# iot_ambilamp.net
KiCad netlist of a schematic drawn in EAGLE
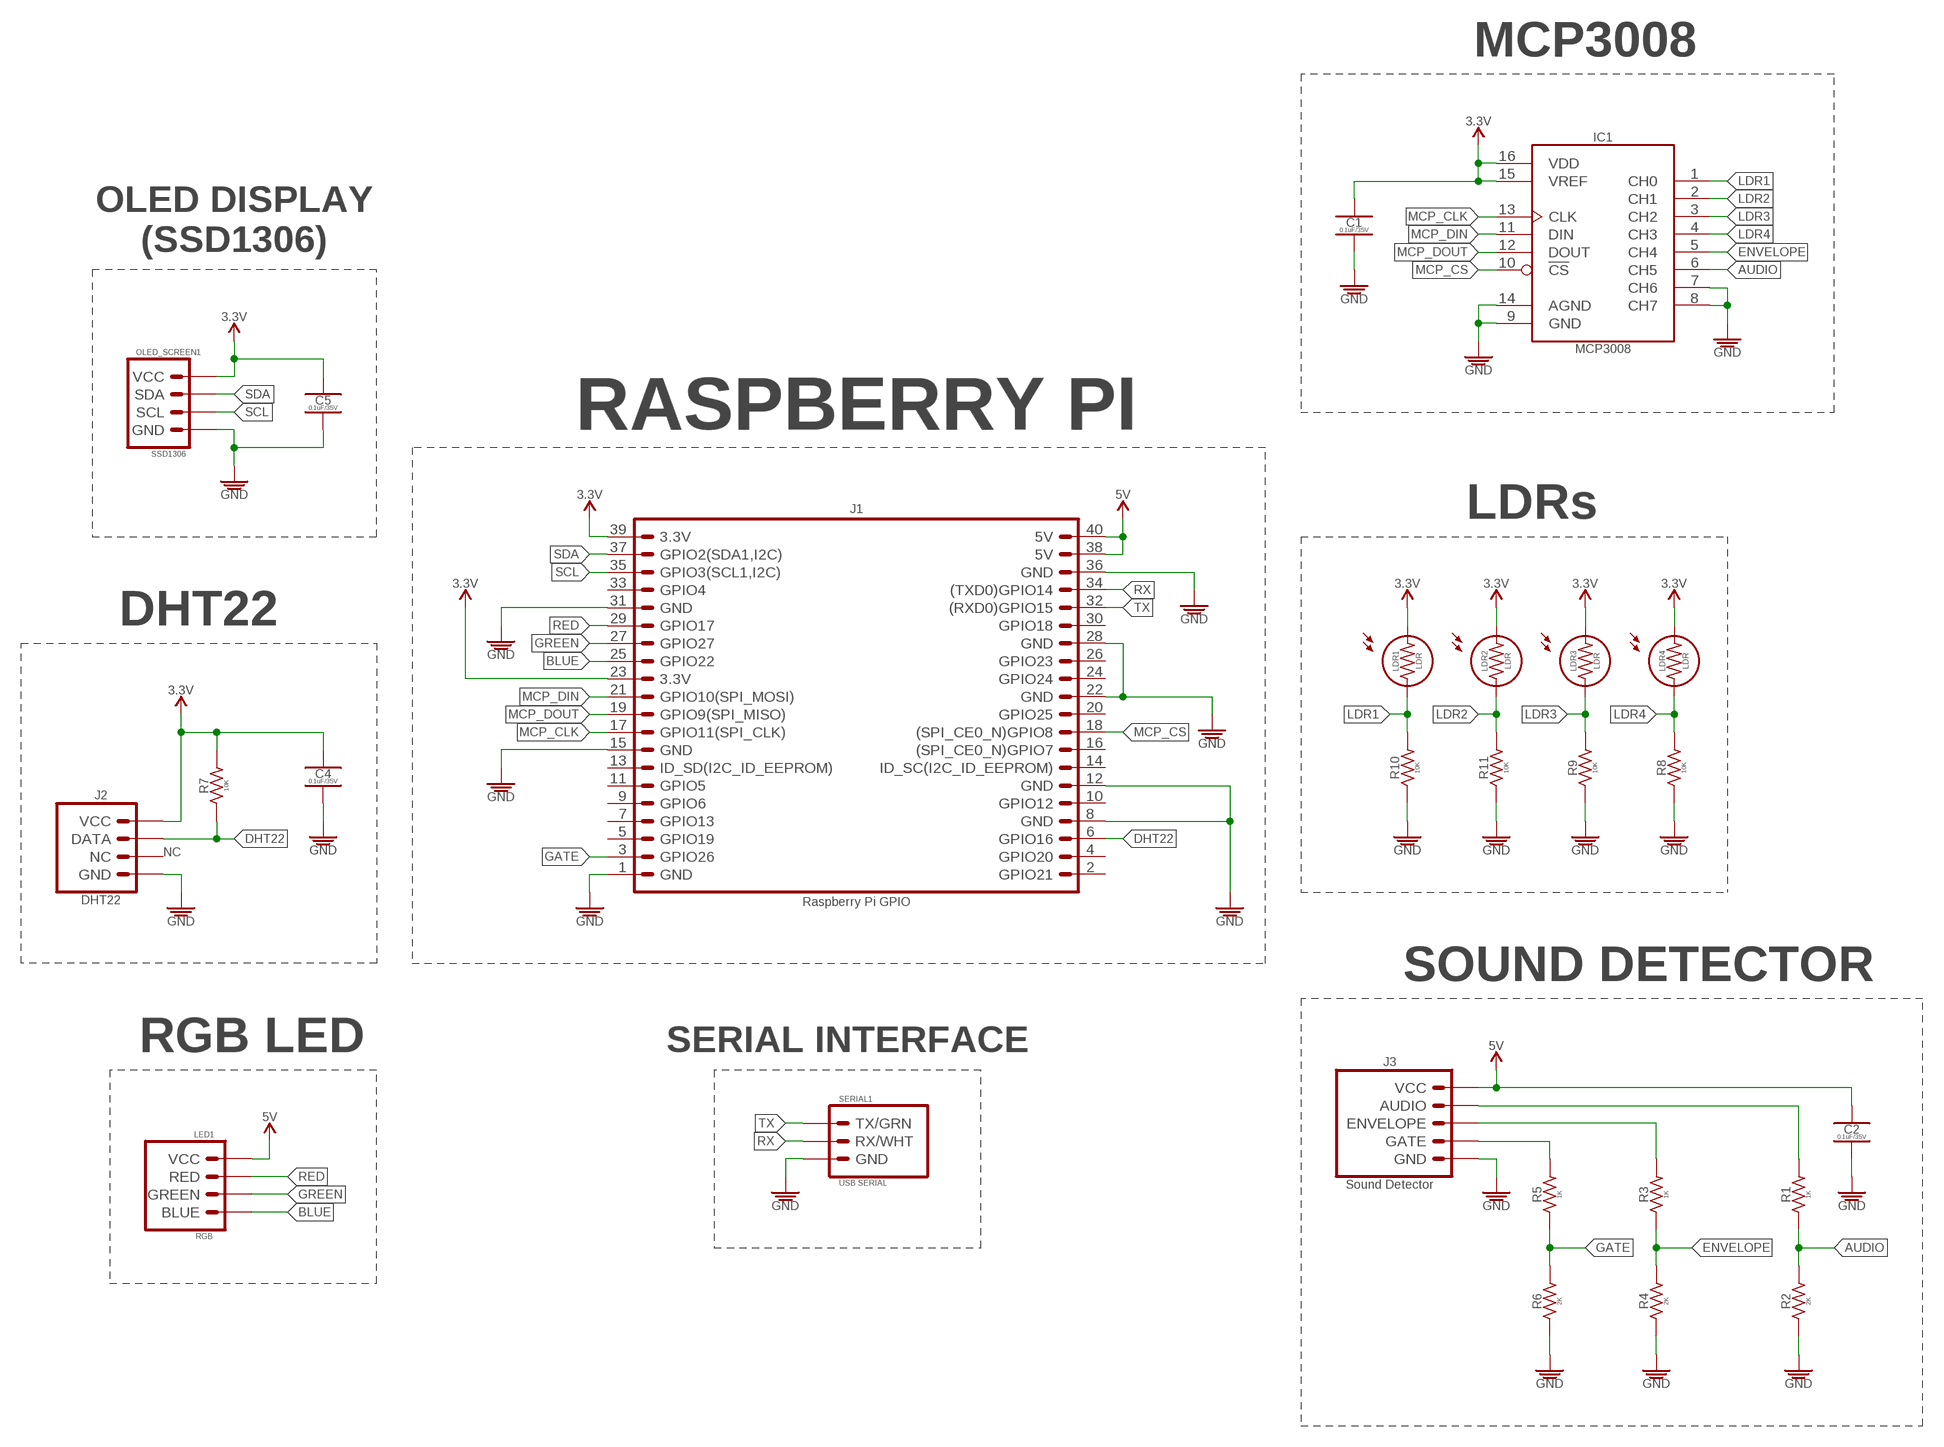
[diagram p0: schematic, sheet 1]

(export (version "E")
  (design (tool "Eeschema 10.0.6"))
  (components
    (comp (ref "C1")
      (value "0.1uF/35V")
      (footprint "eagle-import:CAPC2012X95_SMD-0805")
      (fields (field (name "MFR") "Taiyo Yuden") (field (name "MPN") "GMK212BJ104KGHT"))
      (libsource (lib "eagle-import") (part "0.1UF_SMD-0805_35V-10%"))
    )
    (comp (ref "C2")
      (value "0.1uF/35V")
      (footprint "eagle-import:CAPC2012X95_SMD-0805")
      (fields (field (name "MFR") "Taiyo Yuden") (field (name "MPN") "GMK212BJ104KGHT"))
      (libsource (lib "eagle-import") (part "0.1UF_SMD-0805_35V-10%"))
    )
    (comp (ref "C4")
      (value "0.1uF/35V")
      (footprint "eagle-import:CAPC2012X95_SMD-0805")
      (fields (field (name "MFR") "Taiyo Yuden") (field (name "MPN") "GMK212BJ104KGHT"))
      (libsource (lib "eagle-import") (part "0.1UF_SMD-0805_35V-10%"))
    )
    (comp (ref "C5")
      (value "0.1uF/35V")
      (footprint "eagle-import:CAPC2012X95_SMD-0805")
      (fields (field (name "MFR") "Taiyo Yuden") (field (name "MPN") "GMK212BJ104KGHT"))
      (libsource (lib "eagle-import") (part "0.1UF_SMD-0805_35V-10%"))
    )
    (comp (ref "IC1")
      (value "MCP3008")
      (footprint "eagle-import:SOIC127P600X175-16")
      (fields (field (name "MFR") "Microchip Technology") (field (name "MPN") "MCP3008-I/SL"))
      (libsource (lib "eagle-import") (part "MCP3008_ADC_8-CH_10-BIT_SOIC-16"))
    )
    (comp (ref "J1")
      (value "Raspberry Pi GPIO")
      (footprint "eagle-import:HDRVR40W64P254_2X20_5130X500X1350B")
      (fields (field (name "MFR") "SparkFun Electronics") (field (name "MPN") "PRT-14017"))
      (libsource (lib "eagle-import") (part "RPI-GPIO_CONNECTOR_PTH_VERT_FEMALE_2.54MM"))
    )
    (comp (ref "J2")
      (value "DHT22")
      (footprint "eagle-import:TEMPERATURE-SENSOR_DHT22")
      (fields (field (name "MFR") "Adafruit Industries LLC") (field (name "MPN") "385"))
      (libsource (lib "eagle-import") (part "TEMPERATURE-SENSOR_DHT22_DHT22_AM2302_TEMPERATURE-HUMIDITY"))
    )
    (comp (ref "J3")
      (value "Sound Detector")
      (footprint "eagle-import:HDRV5W64P254_1X5_1270X254X838B")
      (fields (field (name "MFR") "SparkFun Electronics") (field (name "MPN") "SEN-12642"))
      (libsource (lib "eagle-import") (part "SOUND-DETECTOR_SPARKFUN_BREAKOUT_PTH_VERT_MALE_2.54MM"))
    )
    (comp (ref "LDR1")
      (value "LDR")
      (footprint "eagle-import:PHOTORESISTOR_TALL")
      (fields (field (name "MFR") "Adafruit Industries LLC") (field (name "MPN") "161"))
      (libsource (lib "eagle-import") (part "PHOTORESISTOR_5MM_TALL"))
    )
    (comp (ref "LDR2")
      (value "LDR")
      (footprint "eagle-import:PHOTORESISTOR_TALL")
      (fields (field (name "MFR") "Adafruit Industries LLC") (field (name "MPN") "161"))
      (libsource (lib "eagle-import") (part "PHOTORESISTOR_5MM_TALL"))
    )
    (comp (ref "LDR3")
      (value "LDR")
      (footprint "eagle-import:PHOTORESISTOR_TALL")
      (fields (field (name "MFR") "Adafruit Industries LLC") (field (name "MPN") "161"))
      (libsource (lib "eagle-import") (part "PHOTORESISTOR_5MM_TALL"))
    )
    (comp (ref "LDR4")
      (value "LDR")
      (footprint "eagle-import:PHOTORESISTOR_TALL")
      (fields (field (name "MFR") "Adafruit Industries LLC") (field (name "MPN") "161"))
      (libsource (lib "eagle-import") (part "PHOTORESISTOR_5MM_TALL"))
    )
    (comp (ref "LED1")
      (value "RGB")
      (footprint "eagle-import:HDRVR4W75P254_1X4_1066X254X850B")
      (fields (field (name "MFR") "Chanzon") (field (name "MPN") "100F5T-YT-RGB-CA"))
      (libsource (lib "eagle-import") (part "LED-5MM-PTH_RGB-CA_PTH_VERT_FEMALE_2.54MM"))
    )
    (comp (ref "OLED_SCREEN1")
      (value "SSD1306")
      (footprint "eagle-import:HDRV4W64P254_1X4_1016X254X838B")
      (fields (field (name "MFR") "Makerfocus"))
      (libsource (lib "eagle-import") (part "SSD1306_OLED_SCREEN_0.96IN_W128-H64_PTH_VERT_MALE_2.54MM"))
    )
    (comp (ref "R1")
      (value "1K")
      (footprint "eagle-import:RESC2012X60_SMD-0805")
      (fields (field (name "MFR") "Yageo") (field (name "MPN") "RC0805JR-071KL"))
      (libsource (lib "eagle-import") (part "1KΩ_SMD-0805_1/8W-5%"))
    )
    (comp (ref "R2")
      (value "2K")
      (footprint "eagle-import:RESC2012X60_SMD-0805")
      (fields (field (name "MFR") "Yageo") (field (name "MPN") "RC0805JR-072KL"))
      (libsource (lib "eagle-import") (part "2KΩ_SMD-0805_1.8W-5%"))
    )
    (comp (ref "R3")
      (value "1K")
      (footprint "eagle-import:RESC2012X60_SMD-0805")
      (fields (field (name "MFR") "Yageo") (field (name "MPN") "RC0805JR-071KL"))
      (libsource (lib "eagle-import") (part "1KΩ_SMD-0805_1/8W-5%"))
    )
    (comp (ref "R4")
      (value "2K")
      (footprint "eagle-import:RESC2012X60_SMD-0805")
      (fields (field (name "MFR") "Yageo") (field (name "MPN") "RC0805JR-072KL"))
      (libsource (lib "eagle-import") (part "2KΩ_SMD-0805_1.8W-5%"))
    )
    (comp (ref "R5")
      (value "1K")
      (footprint "eagle-import:RESC2012X60_SMD-0805")
      (fields (field (name "MFR") "Yageo") (field (name "MPN") "RC0805JR-071KL"))
      (libsource (lib "eagle-import") (part "1KΩ_SMD-0805_1/8W-5%"))
    )
    (comp (ref "R6")
      (value "2K")
      (footprint "eagle-import:RESC2012X60_SMD-0805")
      (fields (field (name "MFR") "Yageo") (field (name "MPN") "RC0805JR-072KL"))
      (libsource (lib "eagle-import") (part "2KΩ_SMD-0805_1.8W-5%"))
    )
    (comp (ref "R7")
      (value "10K")
      (footprint "eagle-import:RESC2012X60_SMD-0805")
      (fields (field (name "MFR") "Yageo") (field (name "MPN") "RC0805JR-0710KL"))
      (libsource (lib "eagle-import") (part "10KΩ_SMD-0805_1/8W-5%"))
    )
    (comp (ref "R8")
      (value "10K")
      (footprint "eagle-import:RESC2012X60_SMD-0805")
      (fields (field (name "MFR") "Yageo") (field (name "MPN") "RC0805JR-0710KL"))
      (libsource (lib "eagle-import") (part "10KΩ_SMD-0805_1/8W-5%"))
    )
    (comp (ref "R9")
      (value "10K")
      (footprint "eagle-import:RESC2012X60_SMD-0805")
      (fields (field (name "MFR") "Yageo") (field (name "MPN") "RC0805JR-0710KL"))
      (libsource (lib "eagle-import") (part "10KΩ_SMD-0805_1/8W-5%"))
    )
    (comp (ref "R10")
      (value "10K")
      (footprint "eagle-import:RESC2012X60_SMD-0805")
      (fields (field (name "MFR") "Yageo") (field (name "MPN") "RC0805JR-0710KL"))
      (libsource (lib "eagle-import") (part "10KΩ_SMD-0805_1/8W-5%"))
    )
    (comp (ref "R11")
      (value "10K")
      (footprint "eagle-import:RESC2012X60_SMD-0805")
      (fields (field (name "MFR") "Yageo") (field (name "MPN") "RC0805JR-0710KL"))
      (libsource (lib "eagle-import") (part "10KΩ_SMD-0805_1/8W-5%"))
    )
    (comp (ref "SERIAL1")
      (value "USB SERIAL")
      (footprint "eagle-import:HDRV3W64P254_1X3_762X254X838B_USB-SERIAL-CABLE")
      (fields (field (name "MFR") "Adafruit Industries LLC") (field (name "MPN") "954"))
      (libsource (lib "eagle-import") (part "USB_SERIAL_CABLE_PL-2303_3.3V_PTH_VERT_MALE_2.54MM_NO-PWR"))
    )
  )
  (nets
    (net (code "1") (name "3.3V") (class "Default")
      (node (ref "C1") (pin "1") (pinfunction "1_1") (pintype "passive"))
      (node (ref "C4") (pin "1") (pinfunction "1_1") (pintype "passive"))
      (node (ref "C5") (pin "1") (pinfunction "1_1") (pintype "passive"))
      (node (ref "IC1") (pin "15") (pinfunction "VREF_15") (pintype "input"))
      (node (ref "IC1") (pin "16") (pinfunction "VDD_16") (pintype "power_in"))
      (node (ref "J1") (pin "23") (pinfunction "3.3V_23") (pintype "bidirectional"))
      (node (ref "J1") (pin "39") (pinfunction "3.3V_39") (pintype "bidirectional"))
      (node (ref "J2") (pin "VCC") (pinfunction "VCC_VCC") (pintype "passive"))
      (node (ref "LDR1") (pin "P$2") (pinfunction "2_P$2") (pintype "passive"))
      (node (ref "LDR2") (pin "P$2") (pinfunction "2_P$2") (pintype "passive"))
      (node (ref "LDR3") (pin "P$2") (pinfunction "2_P$2") (pintype "passive"))
      (node (ref "LDR4") (pin "P$2") (pinfunction "2_P$2") (pintype "passive"))
      (node (ref "OLED_SCREEN1") (pin "VCC") (pinfunction "VCC_VCC") (pintype "passive"))
      (node (ref "R7") (pin "2") (pinfunction "2_2") (pintype "passive"))
    )
    (net (code "2") (name "5V") (class "Default")
      (node (ref "C2") (pin "1") (pinfunction "1_1") (pintype "passive"))
      (node (ref "J1") (pin "38") (pinfunction "5V_38") (pintype "bidirectional"))
      (node (ref "J1") (pin "40") (pinfunction "5V_40") (pintype "bidirectional"))
      (node (ref "J3") (pin "VCC") (pinfunction "VCC_VCC") (pintype "passive"))
      (node (ref "LED1") (pin "VCC") (pinfunction "VCC_VCC") (pintype "bidirectional"))
    )
    (net (code "3") (name "AUDIO") (class "Default")
      (node (ref "IC1") (pin "6") (pinfunction "CH5_6") (pintype "input"))
      (node (ref "R1") (pin "1") (pinfunction "1_1") (pintype "passive"))
      (node (ref "R2") (pin "2") (pinfunction "2_2") (pintype "passive"))
    )
    (net (code "4") (name "BLUE") (class "Default")
      (node (ref "J1") (pin "25") (pinfunction "GPIO22_25") (pintype "bidirectional"))
      (node (ref "LED1") (pin "BLUE") (pinfunction "BLUE_BLUE") (pintype "bidirectional"))
    )
    (net (code "5") (name "DHT22") (class "Default")
      (node (ref "J1") (pin "6") (pinfunction "GPIO16_6") (pintype "bidirectional"))
      (node (ref "J2") (pin "DATA") (pinfunction "DATA_DATA") (pintype "passive"))
      (node (ref "R7") (pin "1") (pinfunction "1_1") (pintype "passive"))
    )
    (net (code "6") (name "ENVELOPE") (class "Default")
      (node (ref "IC1") (pin "5") (pinfunction "CH4_5") (pintype "input"))
      (node (ref "R3") (pin "1") (pinfunction "1_1") (pintype "passive"))
      (node (ref "R4") (pin "2") (pinfunction "2_2") (pintype "passive"))
    )
    (net (code "7") (name "GATE") (class "Default")
      (node (ref "J1") (pin "3") (pinfunction "GPIO26_3") (pintype "bidirectional"))
      (node (ref "R5") (pin "1") (pinfunction "1_1") (pintype "passive"))
      (node (ref "R6") (pin "2") (pinfunction "2_2") (pintype "passive"))
    )
    (net (code "8") (name "GND") (class "Default")
      (node (ref "C1") (pin "2") (pinfunction "2_2") (pintype "passive"))
      (node (ref "C2") (pin "2") (pinfunction "2_2") (pintype "passive"))
      (node (ref "C4") (pin "2") (pinfunction "2_2") (pintype "passive"))
      (node (ref "C5") (pin "2") (pinfunction "2_2") (pintype "passive"))
      (node (ref "IC1") (pin "14") (pinfunction "AGND_14") (pintype "power_in"))
      (node (ref "IC1") (pin "7") (pinfunction "CH6_7") (pintype "input"))
      (node (ref "IC1") (pin "8") (pinfunction "CH7_8") (pintype "input"))
      (node (ref "IC1") (pin "9") (pinfunction "GND_9") (pintype "power_in"))
      (node (ref "J1") (pin "1") (pinfunction "GND_1") (pintype "bidirectional"))
      (node (ref "J1") (pin "12") (pinfunction "GND_12") (pintype "bidirectional"))
      (node (ref "J1") (pin "15") (pinfunction "GND_15") (pintype "bidirectional"))
      (node (ref "J1") (pin "22") (pinfunction "GND_22") (pintype "bidirectional"))
      (node (ref "J1") (pin "28") (pinfunction "GND_28") (pintype "bidirectional"))
      (node (ref "J1") (pin "31") (pinfunction "GND_31") (pintype "bidirectional"))
      (node (ref "J1") (pin "36") (pinfunction "GND_36") (pintype "bidirectional"))
      (node (ref "J1") (pin "8") (pinfunction "GND_8") (pintype "bidirectional"))
      (node (ref "J2") (pin "GND") (pinfunction "GND_GND") (pintype "passive"))
      (node (ref "J3") (pin "GND") (pinfunction "GND_GND") (pintype "passive"))
      (node (ref "OLED_SCREEN1") (pin "GND") (pinfunction "GND_GND") (pintype "passive"))
      (node (ref "R10") (pin "1") (pinfunction "1_1") (pintype "passive"))
      (node (ref "R11") (pin "1") (pinfunction "1_1") (pintype "passive"))
      (node (ref "R2") (pin "1") (pinfunction "1_1") (pintype "passive"))
      (node (ref "R4") (pin "1") (pinfunction "1_1") (pintype "passive"))
      (node (ref "R6") (pin "1") (pinfunction "1_1") (pintype "passive"))
      (node (ref "R8") (pin "1") (pinfunction "1_1") (pintype "passive"))
      (node (ref "R9") (pin "1") (pinfunction "1_1") (pintype "passive"))
      (node (ref "SERIAL1") (pin "GND") (pinfunction "GND_GND") (pintype "passive"))
    )
    (net (code "9") (name "GREEN") (class "Default")
      (node (ref "J1") (pin "27") (pinfunction "GPIO27_27") (pintype "bidirectional"))
      (node (ref "LED1") (pin "GREEN") (pinfunction "GREEN_GREEN") (pintype "bidirectional"))
    )
    (net (code "10") (name "LDR1") (class "Default")
      (node (ref "IC1") (pin "1") (pinfunction "CH0_1") (pintype "input"))
      (node (ref "LDR1") (pin "P$1") (pinfunction "1_P$1") (pintype "passive"))
      (node (ref "R10") (pin "2") (pinfunction "2_2") (pintype "passive"))
    )
    (net (code "11") (name "LDR2") (class "Default")
      (node (ref "IC1") (pin "2") (pinfunction "CH1_2") (pintype "input"))
      (node (ref "LDR2") (pin "P$1") (pinfunction "1_P$1") (pintype "passive"))
      (node (ref "R11") (pin "2") (pinfunction "2_2") (pintype "passive"))
    )
    (net (code "12") (name "LDR3") (class "Default")
      (node (ref "IC1") (pin "3") (pinfunction "CH2_3") (pintype "input"))
      (node (ref "LDR3") (pin "P$1") (pinfunction "1_P$1") (pintype "passive"))
      (node (ref "R9") (pin "2") (pinfunction "2_2") (pintype "passive"))
    )
    (net (code "13") (name "LDR4") (class "Default")
      (node (ref "IC1") (pin "4") (pinfunction "CH3_4") (pintype "input"))
      (node (ref "LDR4") (pin "P$1") (pinfunction "1_P$1") (pintype "passive"))
      (node (ref "R8") (pin "2") (pinfunction "2_2") (pintype "passive"))
    )
    (net (code "14") (name "MCP_CLK") (class "Default")
      (node (ref "IC1") (pin "13") (pinfunction "CLK_13") (pintype "input"))
      (node (ref "J1") (pin "17") (pinfunction "GPIO11(SPI_CLK)_17") (pintype "bidirectional"))
    )
    (net (code "15") (name "MCP_CS") (class "Default")
      (node (ref "IC1") (pin "10") (pinfunction "~{CS}_10") (pintype "input"))
      (node (ref "J1") (pin "18") (pinfunction "(SPI_CE0_N)GPIO8_18") (pintype "bidirectional"))
    )
    (net (code "16") (name "MCP_DIN") (class "Default")
      (node (ref "IC1") (pin "11") (pinfunction "DIN_11") (pintype "input"))
      (node (ref "J1") (pin "21") (pinfunction "GPIO10(SPI_MOSI)_21") (pintype "bidirectional"))
    )
    (net (code "17") (name "MCP_DOUT") (class "Default")
      (node (ref "IC1") (pin "12") (pinfunction "DOUT_12") (pintype "output"))
      (node (ref "J1") (pin "19") (pinfunction "GPIO9(SPI_MISO)_19") (pintype "bidirectional"))
    )
    (net (code "18") (name "Net-(J3-PadAUDIO)") (class "Default")
      (node (ref "J3") (pin "AUDIO") (pinfunction "AUDIO_AUDIO") (pintype "passive"))
      (node (ref "R1") (pin "2") (pinfunction "2_2") (pintype "passive"))
    )
    (net (code "19") (name "Net-(J3-PadENVELOPE)") (class "Default")
      (node (ref "J3") (pin "ENVELOPE") (pinfunction "ENVELOPE_ENVELOPE") (pintype "passive"))
      (node (ref "R3") (pin "2") (pinfunction "2_2") (pintype "passive"))
    )
    (net (code "20") (name "Net-(J3-PadGATE)") (class "Default")
      (node (ref "J3") (pin "GATE") (pinfunction "GATE_GATE") (pintype "passive"))
      (node (ref "R5") (pin "2") (pinfunction "2_2") (pintype "passive"))
    )
    (net (code "21") (name "RED") (class "Default")
      (node (ref "J1") (pin "29") (pinfunction "GPIO17_29") (pintype "bidirectional"))
      (node (ref "LED1") (pin "RED") (pinfunction "RED_RED") (pintype "bidirectional"))
    )
    (net (code "22") (name "RX") (class "Default")
      (node (ref "J1") (pin "34") (pinfunction "(TXD0)GPIO14_34") (pintype "bidirectional"))
      (node (ref "SERIAL1") (pin "RX/WHT") (pinfunction "RX/WHT_RX/WHT") (pintype "passive"))
    )
    (net (code "23") (name "SCL") (class "Default")
      (node (ref "J1") (pin "35") (pinfunction "GPIO3(SCL1,I2C)_35") (pintype "bidirectional"))
      (node (ref "OLED_SCREEN1") (pin "SCL") (pinfunction "SCL_SCL") (pintype "passive"))
    )
    (net (code "24") (name "SDA") (class "Default")
      (node (ref "J1") (pin "37") (pinfunction "GPIO2(SDA1,I2C)_37") (pintype "bidirectional"))
      (node (ref "OLED_SCREEN1") (pin "SDA") (pinfunction "SDA_SDA") (pintype "passive"))
    )
    (net (code "25") (name "TX") (class "Default")
      (node (ref "J1") (pin "32") (pinfunction "(RXD0)GPIO15_32") (pintype "bidirectional"))
      (node (ref "SERIAL1") (pin "TX/GRN") (pinfunction "TX/GRN_TX/GRN") (pintype "passive"))
    )
    (net (code "26") (name "unconnected-(J1-(SPI_CE0_N)GPIO7-Pad16)") (class "Default")
      (node (ref "J1") (pin "16") (pinfunction "(SPI_CE0_N)GPIO7_16") (pintype "bidirectional"))
    )
    (net (code "27") (name "unconnected-(J1-GPIO4-Pad33)") (class "Default")
      (node (ref "J1") (pin "33") (pinfunction "GPIO4_33") (pintype "bidirectional"))
    )
    (net (code "28") (name "unconnected-(J1-GPIO5-Pad11)") (class "Default")
      (node (ref "J1") (pin "11") (pinfunction "GPIO5_11") (pintype "bidirectional"))
    )
    (net (code "29") (name "unconnected-(J1-GPIO6-Pad9)") (class "Default")
      (node (ref "J1") (pin "9") (pinfunction "GPIO6_9") (pintype "bidirectional"))
    )
    (net (code "30") (name "unconnected-(J1-GPIO12-Pad10)") (class "Default")
      (node (ref "J1") (pin "10") (pinfunction "GPIO12_10") (pintype "bidirectional"))
    )
    (net (code "31") (name "unconnected-(J1-GPIO13-Pad7)") (class "Default")
      (node (ref "J1") (pin "7") (pinfunction "GPIO13_7") (pintype "bidirectional"))
    )
    (net (code "32") (name "unconnected-(J1-GPIO18-Pad30)") (class "Default")
      (node (ref "J1") (pin "30") (pinfunction "GPIO18_30") (pintype "bidirectional"))
    )
    (net (code "33") (name "unconnected-(J1-GPIO19-Pad5)") (class "Default")
      (node (ref "J1") (pin "5") (pinfunction "GPIO19_5") (pintype "bidirectional"))
    )
    (net (code "34") (name "unconnected-(J1-GPIO20-Pad4)") (class "Default")
      (node (ref "J1") (pin "4") (pinfunction "GPIO20_4") (pintype "bidirectional"))
    )
    (net (code "35") (name "unconnected-(J1-GPIO21-Pad2)") (class "Default")
      (node (ref "J1") (pin "2") (pinfunction "GPIO21_2") (pintype "bidirectional"))
    )
    (net (code "36") (name "unconnected-(J1-GPIO23-Pad26)") (class "Default")
      (node (ref "J1") (pin "26") (pinfunction "GPIO23_26") (pintype "bidirectional"))
    )
    (net (code "37") (name "unconnected-(J1-GPIO24-Pad24)") (class "Default")
      (node (ref "J1") (pin "24") (pinfunction "GPIO24_24") (pintype "bidirectional"))
    )
    (net (code "38") (name "unconnected-(J1-GPIO25-Pad20)") (class "Default")
      (node (ref "J1") (pin "20") (pinfunction "GPIO25_20") (pintype "bidirectional"))
    )
    (net (code "39") (name "unconnected-(J1-ID_SC(I2C_ID_EEPROM)-Pad14)") (class "Default")
      (node (ref "J1") (pin "14") (pinfunction "ID_SC(I2C_ID_EEPROM)_14") (pintype "bidirectional"))
    )
    (net (code "40") (name "unconnected-(J1-ID_SD(I2C_ID_EEPROM)-Pad13)") (class "Default")
      (node (ref "J1") (pin "13") (pinfunction "ID_SD(I2C_ID_EEPROM)_13") (pintype "bidirectional"))
    )
    (net (code "41") (name "unconnected-(J2-PadNC)") (class "Default")
      (node (ref "J2") (pin "NC") (pinfunction "NC_NC") (pintype "no_connect"))
    )
  )
)
